# Pressure.net
KiCad netlist of a schematic drawn in EAGLE
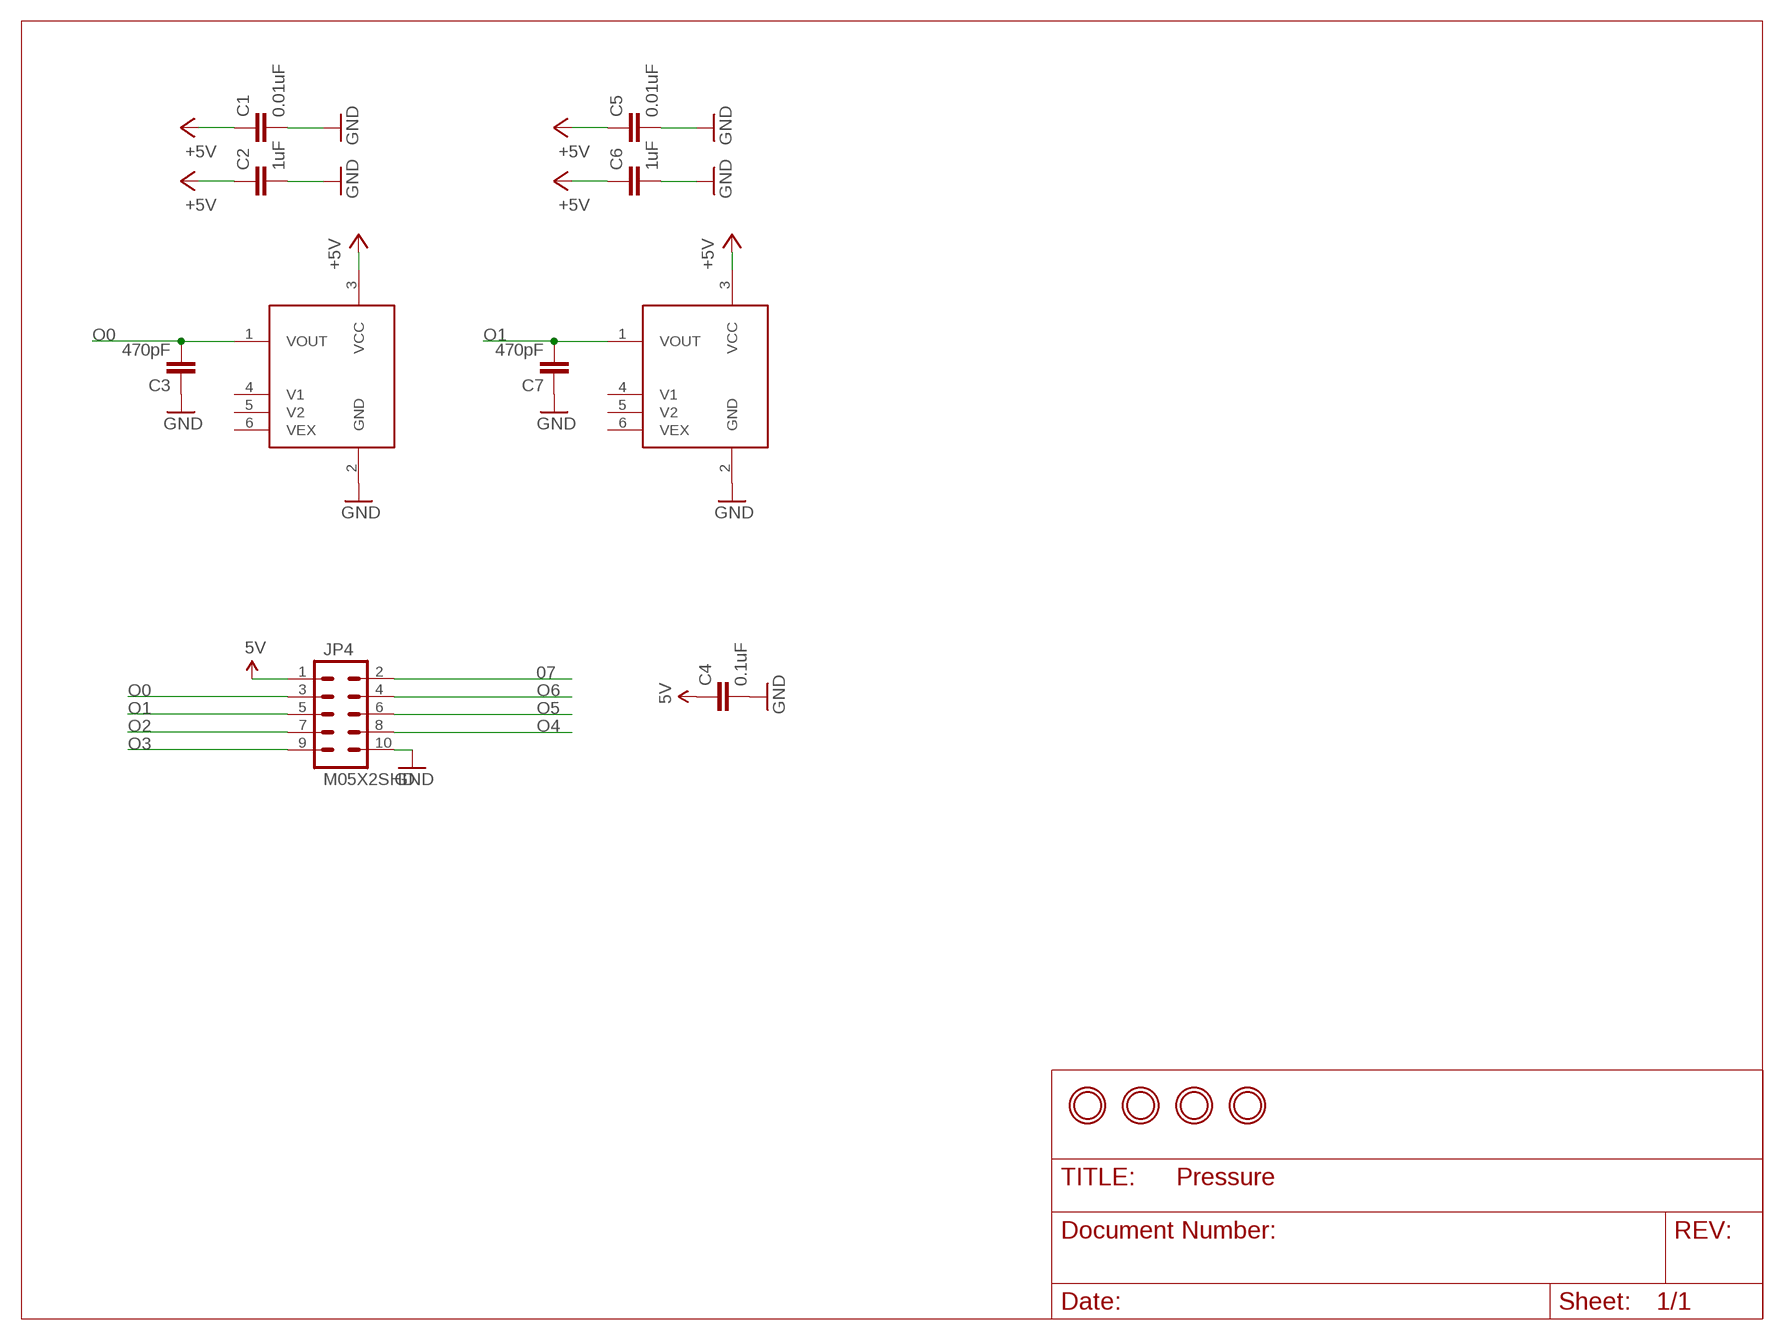
[diagram p0: schematic, sheet 1]

(export (version "E")
  (design (tool "Eeschema 10.0.6"))
  (components
    (comp (ref "C1")
      (value "0.01uF")
      (footprint "eagle-import:0805")
      (libsource (lib "eagle-import") (part "CAP0805"))
    )
    (comp (ref "C2")
      (value "1uF")
      (footprint "eagle-import:0805")
      (libsource (lib "eagle-import") (part "CAP0805"))
    )
    (comp (ref "C3")
      (value "470pF")
      (footprint "eagle-import:0805")
      (libsource (lib "eagle-import") (part "CAP0805"))
    )
    (comp (ref "C4")
      (value "0.1uF")
      (footprint "eagle-import:0805")
      (libsource (lib "eagle-import") (part "CAP0805"))
    )
    (comp (ref "C5")
      (value "0.01uF")
      (footprint "eagle-import:0805")
      (libsource (lib "eagle-import") (part "CAP0805"))
    )
    (comp (ref "C6")
      (value "1uF")
      (footprint "eagle-import:0805")
      (libsource (lib "eagle-import") (part "CAP0805"))
    )
    (comp (ref "C7")
      (value "470pF")
      (footprint "eagle-import:0805")
      (libsource (lib "eagle-import") (part "CAP0805"))
    )
    (comp (ref "JP4")
      (value "M05X2SHD")
      (footprint "eagle-import:2X5-SHROUDED")
      (libsource (lib "eagle-import") (part "M05X2SHD"))
    )
    (comp (ref "U$1")
      (value "MPX5700")
      (footprint "eagle-import:MPX5700ASX")
      (libsource (lib "eagle-import") (part "MPX5700"))
    )
    (comp (ref "U$2")
      (value "MPX5700")
      (footprint "eagle-import:MPX5700ASX")
      (libsource (lib "eagle-import") (part "MPX5700"))
    )
    (comp (ref "U$9")
      (value "MOUNTINGHOLE2.0")
      (footprint "eagle-import:MOUNTINGHOLE_2.0_PLATED")
      (libsource (lib "eagle-import") (part "MOUNTINGHOLE2.0"))
    )
    (comp (ref "U$10")
      (value "MOUNTINGHOLE2.0")
      (footprint "eagle-import:MOUNTINGHOLE_2.0_PLATED")
      (libsource (lib "eagle-import") (part "MOUNTINGHOLE2.0"))
    )
    (comp (ref "U$11")
      (value "MOUNTINGHOLE2.0")
      (footprint "eagle-import:MOUNTINGHOLE_2.0_PLATED")
      (libsource (lib "eagle-import") (part "MOUNTINGHOLE2.0"))
    )
    (comp (ref "U$12")
      (value "MOUNTINGHOLE2.0")
      (footprint "eagle-import:MOUNTINGHOLE_2.0_PLATED")
      (libsource (lib "eagle-import") (part "MOUNTINGHOLE2.0"))
    )
  )
  (nets
    (net (code "1") (name "+5V") (class "Default")
      (node (ref "C1") (pin "1") (pinfunction "1_1") (pintype "passive"))
      (node (ref "C2") (pin "1") (pinfunction "1_1") (pintype "passive"))
      (node (ref "C5") (pin "1") (pinfunction "1_1") (pintype "passive"))
      (node (ref "C6") (pin "1") (pinfunction "1_1") (pintype "passive"))
      (node (ref "U$1") (pin "3") (pinfunction "VCC_3") (pintype "bidirectional"))
      (node (ref "U$2") (pin "3") (pinfunction "VCC_3") (pintype "bidirectional"))
    )
    (net (code "2") (name "/07") (class "Default")
      (node (ref "JP4") (pin "2") (pinfunction "2_2") (pintype "passive"))
    )
    (net (code "3") (name "/O0") (class "Default")
      (node (ref "C3") (pin "2") (pinfunction "2_2") (pintype "passive"))
      (node (ref "JP4") (pin "3") (pinfunction "3_3") (pintype "passive"))
      (node (ref "U$1") (pin "1") (pinfunction "VOUT_1") (pintype "bidirectional"))
    )
    (net (code "4") (name "/O1") (class "Default")
      (node (ref "C7") (pin "2") (pinfunction "2_2") (pintype "passive"))
      (node (ref "JP4") (pin "5") (pinfunction "5_5") (pintype "passive"))
      (node (ref "U$2") (pin "1") (pinfunction "VOUT_1") (pintype "bidirectional"))
    )
    (net (code "5") (name "/O2") (class "Default")
      (node (ref "JP4") (pin "7") (pinfunction "7_7") (pintype "passive"))
    )
    (net (code "6") (name "/O3") (class "Default")
      (node (ref "JP4") (pin "9") (pinfunction "9_9") (pintype "passive"))
    )
    (net (code "7") (name "/O4") (class "Default")
      (node (ref "JP4") (pin "8") (pinfunction "8_8") (pintype "passive"))
    )
    (net (code "8") (name "/O5") (class "Default")
      (node (ref "JP4") (pin "6") (pinfunction "6_6") (pintype "passive"))
    )
    (net (code "9") (name "/O6") (class "Default")
      (node (ref "JP4") (pin "4") (pinfunction "4_4") (pintype "passive"))
    )
    (net (code "10") (name "5V") (class "Default")
      (node (ref "C4") (pin "1") (pinfunction "1_1") (pintype "passive"))
      (node (ref "JP4") (pin "1") (pinfunction "1_1") (pintype "passive"))
    )
    (net (code "11") (name "GND") (class "Default")
      (node (ref "C1") (pin "2") (pinfunction "2_2") (pintype "passive"))
      (node (ref "C2") (pin "2") (pinfunction "2_2") (pintype "passive"))
      (node (ref "C3") (pin "1") (pinfunction "1_1") (pintype "passive"))
      (node (ref "C4") (pin "2") (pinfunction "2_2") (pintype "passive"))
      (node (ref "C5") (pin "2") (pinfunction "2_2") (pintype "passive"))
      (node (ref "C6") (pin "2") (pinfunction "2_2") (pintype "passive"))
      (node (ref "C7") (pin "1") (pinfunction "1_1") (pintype "passive"))
      (node (ref "JP4") (pin "10") (pinfunction "10_10") (pintype "passive"))
      (node (ref "U$1") (pin "2") (pinfunction "GND_2") (pintype "bidirectional"))
      (node (ref "U$2") (pin "2") (pinfunction "GND_2") (pintype "bidirectional"))
    )
    (net (code "12") (name "unconnected-(U$1-V1-Pad4)") (class "Default")
      (node (ref "U$1") (pin "4") (pinfunction "V1_4") (pintype "bidirectional"))
    )
    (net (code "13") (name "unconnected-(U$1-V2-Pad5)") (class "Default")
      (node (ref "U$1") (pin "5") (pinfunction "V2_5") (pintype "bidirectional"))
    )
    (net (code "14") (name "unconnected-(U$1-VEX-Pad6)") (class "Default")
      (node (ref "U$1") (pin "6") (pinfunction "VEX_6") (pintype "bidirectional"))
    )
    (net (code "15") (name "unconnected-(U$2-V1-Pad4)") (class "Default")
      (node (ref "U$2") (pin "4") (pinfunction "V1_4") (pintype "bidirectional"))
    )
    (net (code "16") (name "unconnected-(U$2-V2-Pad5)") (class "Default")
      (node (ref "U$2") (pin "5") (pinfunction "V2_5") (pintype "bidirectional"))
    )
    (net (code "17") (name "unconnected-(U$2-VEX-Pad6)") (class "Default")
      (node (ref "U$2") (pin "6") (pinfunction "VEX_6") (pintype "bidirectional"))
    )
  )
)
